# AppleTV.net
KiCad netlist of a schematic drawn in EAGLE
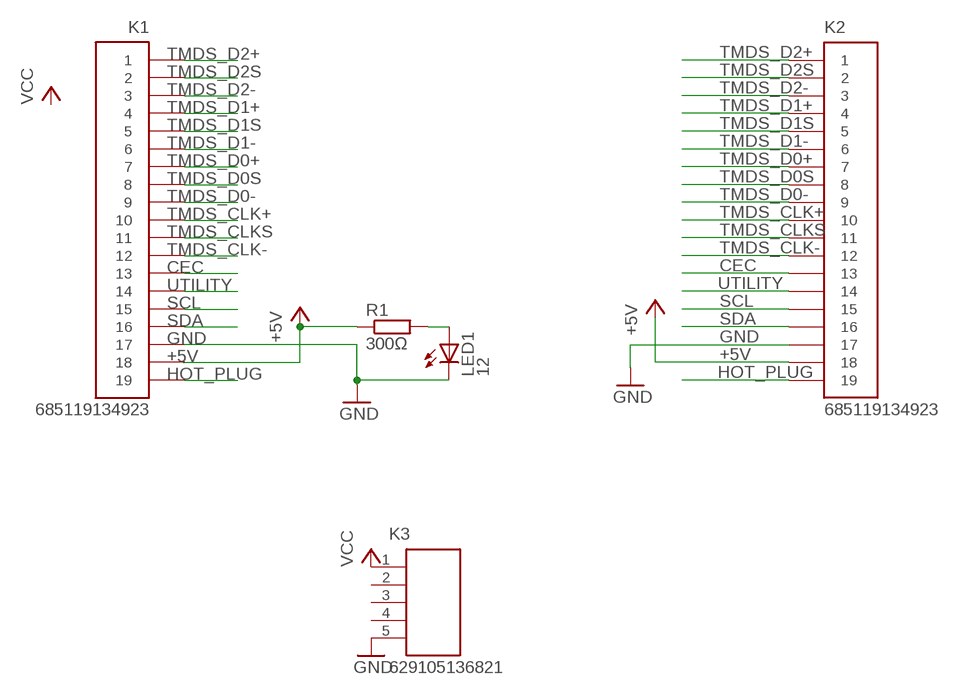
[diagram p0: schematic, sheet 1]

(export (version "E")
  (design (tool "Eeschema 10.0.6"))
  (components
    (comp (ref "K1")
      (value "685119134923")
      (footprint "eagle-import:685119134923")
      (libsource (lib "eagle-import") (part "685119134923"))
    )
    (comp (ref "K2")
      (value "685119134923")
      (footprint "eagle-import:685119134923")
      (libsource (lib "eagle-import") (part "685119134923"))
    )
    (comp (ref "K3")
      (value "629105136821")
      (footprint "eagle-import:629105136821")
      (libsource (lib "eagle-import") (part "629105136821"))
    )
    (comp (ref "LED1")
      (value "12")
      (footprint "eagle-import:CHIPLED_1206")
      (libsource (lib "eagle-import") (part "LEDCHIPLED_1206"))
    )
    (comp (ref "R1")
      (value "300Ω")
      (footprint "eagle-import:R0805")
      (libsource (lib "eagle-import") (part "R-EU_R0805"))
    )
  )
  (nets
    (net (code "1") (name "+5V") (class "Default")
      (node (ref "K2") (pin "18") (pinfunction "18_18") (pintype "passive"))
      (node (ref "R1") (pin "1") (pinfunction "1_1") (pintype "passive"))
    )
    (net (code "2") (name "/CEC") (class "Default")
      (node (ref "K1") (pin "13") (pinfunction "13_13") (pintype "passive"))
      (node (ref "K2") (pin "13") (pinfunction "13_13") (pintype "passive"))
    )
    (net (code "3") (name "/HOT_PLUG") (class "Default")
      (node (ref "K1") (pin "19") (pinfunction "19_19") (pintype "passive"))
      (node (ref "K2") (pin "19") (pinfunction "19_19") (pintype "passive"))
    )
    (net (code "4") (name "/SCL") (class "Default")
      (node (ref "K1") (pin "15") (pinfunction "15_15") (pintype "passive"))
      (node (ref "K2") (pin "15") (pinfunction "15_15") (pintype "passive"))
    )
    (net (code "5") (name "/SDA") (class "Default")
      (node (ref "K1") (pin "16") (pinfunction "16_16") (pintype "passive"))
      (node (ref "K2") (pin "16") (pinfunction "16_16") (pintype "passive"))
    )
    (net (code "6") (name "/TMDS_CLK+") (class "Default")
      (node (ref "K1") (pin "10") (pinfunction "10_10") (pintype "passive"))
      (node (ref "K2") (pin "10") (pinfunction "10_10") (pintype "passive"))
    )
    (net (code "7") (name "/TMDS_CLK-") (class "Default")
      (node (ref "K1") (pin "12") (pinfunction "12_12") (pintype "passive"))
      (node (ref "K2") (pin "12") (pinfunction "12_12") (pintype "passive"))
    )
    (net (code "8") (name "/TMDS_CLKS") (class "Default")
      (node (ref "K1") (pin "11") (pinfunction "11_11") (pintype "passive"))
      (node (ref "K2") (pin "11") (pinfunction "11_11") (pintype "passive"))
    )
    (net (code "9") (name "/TMDS_D0+") (class "Default")
      (node (ref "K1") (pin "7") (pinfunction "7_7") (pintype "passive"))
      (node (ref "K2") (pin "7") (pinfunction "7_7") (pintype "passive"))
    )
    (net (code "10") (name "/TMDS_D0-") (class "Default")
      (node (ref "K1") (pin "9") (pinfunction "9_9") (pintype "passive"))
      (node (ref "K2") (pin "9") (pinfunction "9_9") (pintype "passive"))
    )
    (net (code "11") (name "/TMDS_D0S") (class "Default")
      (node (ref "K1") (pin "8") (pinfunction "8_8") (pintype "passive"))
      (node (ref "K2") (pin "8") (pinfunction "8_8") (pintype "passive"))
    )
    (net (code "12") (name "/TMDS_D1+") (class "Default")
      (node (ref "K1") (pin "4") (pinfunction "4_4") (pintype "passive"))
      (node (ref "K2") (pin "4") (pinfunction "4_4") (pintype "passive"))
    )
    (net (code "13") (name "/TMDS_D1-") (class "Default")
      (node (ref "K1") (pin "6") (pinfunction "6_6") (pintype "passive"))
      (node (ref "K2") (pin "6") (pinfunction "6_6") (pintype "passive"))
    )
    (net (code "14") (name "/TMDS_D1S") (class "Default")
      (node (ref "K1") (pin "5") (pinfunction "5_5") (pintype "passive"))
      (node (ref "K2") (pin "5") (pinfunction "5_5") (pintype "passive"))
    )
    (net (code "15") (name "/TMDS_D2+") (class "Default")
      (node (ref "K1") (pin "1") (pinfunction "1_1") (pintype "passive"))
      (node (ref "K2") (pin "1") (pinfunction "1_1") (pintype "passive"))
    )
    (net (code "16") (name "/TMDS_D2-") (class "Default")
      (node (ref "K1") (pin "3") (pinfunction "3_3") (pintype "passive"))
      (node (ref "K2") (pin "3") (pinfunction "3_3") (pintype "passive"))
    )
    (net (code "17") (name "/TMDS_D2S") (class "Default")
      (node (ref "K1") (pin "2") (pinfunction "2_2") (pintype "passive"))
      (node (ref "K2") (pin "2") (pinfunction "2_2") (pintype "passive"))
    )
    (net (code "18") (name "/UTILITY") (class "Default")
      (node (ref "K1") (pin "14") (pinfunction "14_14") (pintype "passive"))
      (node (ref "K2") (pin "14") (pinfunction "14_14") (pintype "passive"))
    )
    (net (code "19") (name "GND") (class "Default")
      (node (ref "K1") (pin "17") (pinfunction "17_17") (pintype "passive"))
      (node (ref "K2") (pin "17") (pinfunction "17_17") (pintype "passive"))
      (node (ref "K3") (pin "5") (pinfunction "5_5") (pintype "passive"))
      (node (ref "LED1") (pin "C") (pinfunction "C_C") (pintype "passive"))
    )
    (net (code "20") (name "Net-(LED1-PadA)") (class "Default")
      (node (ref "LED1") (pin "A") (pinfunction "A_A") (pintype "passive"))
      (node (ref "R1") (pin "2") (pinfunction "2_2") (pintype "passive"))
    )
    (net (code "21") (name "VCC") (class "Default")
      (node (ref "K3") (pin "1") (pinfunction "1_1") (pintype "passive"))
    )
    (net (code "22") (name "unconnected-(K1-Pad18)") (class "Default")
      (node (ref "K1") (pin "18") (pinfunction "18_18") (pintype "passive"))
    )
    (net (code "23") (name "unconnected-(K3-Pad2)") (class "Default")
      (node (ref "K3") (pin "2") (pinfunction "2_2") (pintype "passive"))
    )
    (net (code "24") (name "unconnected-(K3-Pad3)") (class "Default")
      (node (ref "K3") (pin "3") (pinfunction "3_3") (pintype "passive"))
    )
    (net (code "25") (name "unconnected-(K3-Pad4)") (class "Default")
      (node (ref "K3") (pin "4") (pinfunction "4_4") (pintype "passive"))
    )
  )
)
